# Sheet2.net
KiCad netlist of a schematic drawn in Altium Designer
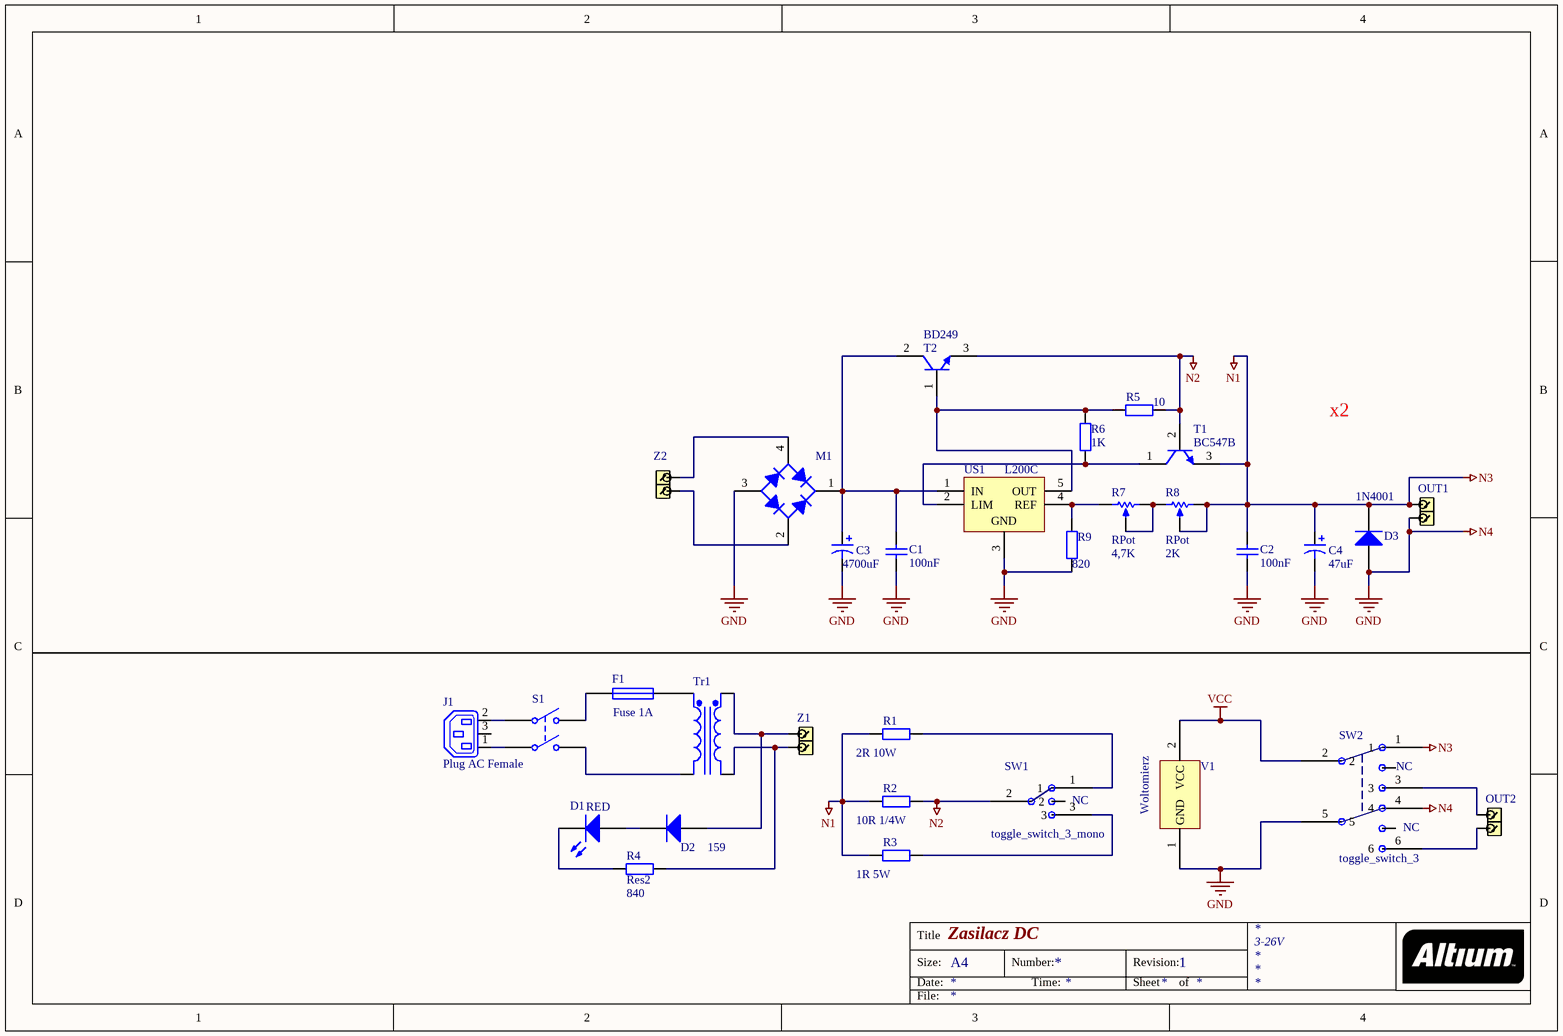
[diagram p0: Sheet2.SchDoc]

(export (version "E")
  (design (tool "Eeschema 10.0.6"))
  (components
    (comp (ref "C1")
      (value "100nF")
      (footprint "CAPR2.54-5.1x2.5")
      (description "Capacitor (Semiconductor SIM Model)")
      (fields (field (name "Comment") "Cap Semi") (field (name "PUBLISHER") "Altium Limited"))
      (libsource (lib "Miscellaneous Devices") (part "Cap Semi"))
    )
    (comp (ref "C2")
      (value "100nF")
      (footprint "CAPR2.54-5.1x2.5")
      (description "Capacitor (Semiconductor SIM Model)")
      (fields (field (name "Comment") "Cap Semi") (field (name "PUBLISHER") "Altium Limited"))
      (libsource (lib "Miscellaneous Devices") (part "Cap Semi"))
    )
    (comp (ref "C3")
      (value "4700uF")
      (footprint "CAPPR7.5-16x20")
      (description "Polarized Capacitor (Radial)")
      (fields (field (name "Comment") "Cap Pol1") (field (name "PUBLISHER") "Altium Limited"))
      (libsource (lib "Miscellaneous Devices") (part "Cap Pol1"))
    )
    (comp (ref "C4")
      (value "47uF")
      (footprint "CAPPR5-6.3x15")
      (description "Polarized Capacitor (Radial)")
      (fields (field (name "Comment") "Cap Pol1") (field (name "PUBLISHER") "Altium Limited"))
      (libsource (lib "Miscellaneous Devices") (part "Cap Pol1"))
    )
    (comp (ref "D1")
      (value "RED")
      (footprint "LED-0")
      (description "Typical INFRARED GaAs LED")
      (fields (field (name "PUBLISHER") "Altium Limited"))
      (libsource (lib "Miscellaneous Devices") (part "LED0"))
    )
    (comp (ref "D2")
      (value "159")
      (footprint "SMC")
      (description "Default Diode")
      (fields (field (name "PUBLISHER") "Altium Limited"))
      (libsource (lib "Miscellaneous Devices") (part "Diode"))
    )
    (comp (ref "D3")
      (value "1N4001")
      (footprint "DO-41")
      (description "1 Amp General Purpose Rectifier")
      (fields (field (name "PUBLISHER") "Altium Limited"))
      (libsource (lib "Miscellaneous Devices") (part "Diode 1N4001"))
    )
    (comp (ref "F1")
      (value "Fuse 1A")
      (footprint "PIN-W2/E2.8")
      (description "Fuse")
      (fields (field (name "PUBLISHER") "Altium Limited"))
      (libsource (lib "Miscellaneous Devices") (part "Fuse 1"))
    )
    (comp (ref "J1")
      (value "Plug AC Female")
      (footprint "IEC7-2H3")
      (description "IEC Mains Power Outlet, EN60 320-2-2 F Class I, PC Flange Rear Mount, Chassis Socket")
      (fields (field (name "PUBLISHER") "Altium Limited"))
      (libsource (lib "Miscellaneous Connectors") (part "Plug AC Female"))
    )
    (comp (ref "M1")
      (value "Bridge1")
      (footprint "D-38")
      (description "Full Wave Diode Bridge")
      (fields (field (name "PUBLISHER") "Altium Limited"))
      (libsource (lib "Miscellaneous Devices") (part "Bridge1"))
    )
    (comp (ref "OUT1") (value "ARK") (footprint "ARK2") (libsource (lib "") (part "ARK_1")))
    (comp (ref "OUT2") (value "ARK") (footprint "ARK2") (libsource (lib "") (part "ARK_1")))
    (comp (ref "R1")
      (value "2R 10W")
      (footprint "AXIAL-0.4")
      (description "Resistor")
      (fields (field (name "Comment") "Res2") (field (name "PUBLISHER") "Altium Limited"))
      (libsource (lib "Miscellaneous Devices") (part "Res2"))
    )
    (comp (ref "R2")
      (value "10R 1/4W")
      (footprint "AXIAL-0.4")
      (description "Resistor")
      (fields (field (name "Comment") "Res2") (field (name "PUBLISHER") "Altium Limited"))
      (libsource (lib "Miscellaneous Devices") (part "Res2"))
    )
    (comp (ref "R3")
      (value "1R 5W")
      (footprint "AXIAL-0.4")
      (description "Resistor")
      (fields (field (name "Comment") "Res2") (field (name "PUBLISHER") "Altium Limited"))
      (libsource (lib "Miscellaneous Devices") (part "Res2"))
    )
    (comp (ref "R4")
      (value "Res2")
      (footprint "AXIAL-0.4")
      (description "Resistor")
      (fields (field (name "ALTIUM_VALUE") "840") (field (name "PUBLISHER") "Altium Limited"))
      (libsource (lib "Miscellaneous Devices") (part "Res2"))
    )
    (comp (ref "R5")
      (value "10")
      (footprint "AXIAL-0.4")
      (description "Resistor")
      (fields (field (name "Comment") "Res2") (field (name "PUBLISHER") "Altium Limited"))
      (libsource (lib "Miscellaneous Devices") (part "Res2"))
    )
    (comp (ref "R6")
      (value "1K")
      (footprint "AXIAL-0.4")
      (description "Resistor")
      (fields (field (name "Comment") "Res2") (field (name "PUBLISHER") "Altium Limited"))
      (libsource (lib "") (part "Res2_1"))
    )
    (comp (ref "R7")
      (value "RPot")
      (footprint "VR5")
      (description "Potentiometer")
      (fields (field (name "ALTIUM_VALUE") "4,7K") (field (name "PUBLISHER") "Altium Limited"))
      (libsource (lib "Miscellaneous Devices") (part "RPot"))
    )
    (comp (ref "R8")
      (value "RPot")
      (footprint "VR5")
      (description "Potentiometer")
      (fields (field (name "ALTIUM_VALUE") "2K") (field (name "PUBLISHER") "Altium Limited"))
      (libsource (lib "Miscellaneous Devices") (part "RPot"))
    )
    (comp (ref "R9")
      (value "820")
      (footprint "AXIAL-0.4")
      (description "Resistor")
      (fields (field (name "Comment") "Res2") (field (name "PUBLISHER") "Altium Limited"))
      (libsource (lib "") (part "Res2_2"))
    )
    (comp (ref "S1")
      (value "SW-DPST")
      (footprint "DPST-4")
      (description "Double-Pole, Single-Throw Switch")
      (fields (field (name "PUBLISHER") "Altium Limited"))
      (libsource (lib "Miscellaneous Devices") (part "SW-DPST"))
    )
    (comp (ref "SW1")
      (value "toggle_switch_3_mono")
      (description "Single 3-stage toggle switch")
      (libsource (lib "zasilacz_lib") (part "toggle_switch_3_mono"))
    )
    (comp (ref "SW2")
      (value "toggle_switch_3")
      (description "Dual 3-stage toggle switch")
      (libsource (lib "zasilacz_lib") (part "toggle_switch_3"))
    )
    (comp (ref "T1")
      (value "BC547B")
      (footprint "ONSC-TO-92-3-29-11")
      (description "Amplifier Transistor, NPN Silicon, 3-Pin TO-92, Bulk Box")
      (fields (field (name "MANUFACTURER") "On Semiconductor"))
      (libsource (lib "ON Semi General Purpose Transistors") (part "BC547B"))
    )
    (comp (ref "T2")
      (value "BD249")
      (footprint "ONSC-TO-220-3-221A-09")
      (description "NPN Silicon Power Transistor, 3-Pin TO-220, Tube")
      (fields (field (name "MANUFACTURER") "On Semiconductor") (field (name "PARTNUMBER") "BUV27"))
      (libsource (lib "ON Semi General Purpose Transistors") (part "BUV27"))
    )
    (comp (ref "Tr1")
      (value "Trans Cupl")
      (footprint "TRF_4")
      (description "Transformer (Coupled Inductor Model)")
      (fields (field (name "PUBLISHER") "Altium Limited"))
      (libsource (lib "Miscellaneous Devices") (part "Trans Cupl"))
    )
    (comp (ref "US1")
      (value "L200C")
      (footprint "PentawattV")
      (description "Adjustable Voltage and Current Regulator, 5-Pin Pentawatt, Tube")
      (fields (field (name "PARTNUMBER") "L200CV"))
      (libsource (lib "ST Microelectronics Power Management Linear Regulator") (part "L200CV"))
    )
    (comp (ref "V1") (value "Woltomierz") (libsource (lib "zasilacz_lib") (part "woltomierz")))
    (comp (ref "Z1") (value "~") (footprint "ARK2") (libsource (lib "") (part "ARK_1")))
    (comp (ref "Z2") (value "~") (footprint "ARK2") (libsource (lib "MOJASIM") (part "ARK")))
  )
  (nets
    (net (code "1") (name "GND") (class "Default")
      (node (ref "C1") (pin "1") (pinfunction "1_1") (pintype "passive"))
      (node (ref "C2") (pin "1") (pinfunction "1_1") (pintype "passive"))
      (node (ref "C3") (pin "2") (pinfunction "2_2") (pintype "passive"))
      (node (ref "C4") (pin "2") (pinfunction "2_2") (pintype "passive"))
      (node (ref "D3") (pin "1") (pinfunction "A_1") (pintype "passive"))
      (node (ref "M1") (pin "3") (pinfunction "A_3") (pintype "passive"))
      (node (ref "OUT1") (pin "1") (pinfunction "1_1") (pintype "passive"))
      (node (ref "R9") (pin "1") (pinfunction "1_1") (pintype "passive"))
      (node (ref "SW2") (pin "4") (pinfunction "4_4") (pintype "passive"))
      (node (ref "SW2") (pin "5") (pinfunction "5_5") (pintype "passive"))
      (node (ref "US1") (pin "3") (pinfunction "GND_3") (pintype "power_in"))
      (node (ref "V1") (pin "1") (pinfunction "GND_1") (pintype "passive"))
    )
    (net (code "2") (name "N1") (class "Default")
      (node (ref "C2") (pin "2") (pinfunction "2_2") (pintype "passive"))
      (node (ref "C4") (pin "1") (pinfunction "1_1") (pintype "passive"))
      (node (ref "D3") (pin "2") (pinfunction "K_2") (pintype "passive"))
      (node (ref "OUT1") (pin "2") (pinfunction "2_2") (pintype "passive"))
      (node (ref "R1") (pin "1") (pinfunction "1_1") (pintype "passive"))
      (node (ref "R2") (pin "1") (pinfunction "1_1") (pintype "passive"))
      (node (ref "R3") (pin "1") (pinfunction "1_1") (pintype "passive"))
      (node (ref "R8") (pin "2") (pinfunction "BOT_2") (pintype "passive"))
      (node (ref "R8") (pin "3") (pinfunction "TAP_3") (pintype "passive"))
      (node (ref "SW2") (pin "1") (pinfunction "1_1") (pintype "passive"))
      (node (ref "T1") (pin "3") (pinfunction "E_3") (pintype "passive"))
    )
    (net (code "3") (name "N2") (class "Default")
      (node (ref "R2") (pin "2") (pinfunction "2_2") (pintype "passive"))
      (node (ref "R5") (pin "2") (pinfunction "2_2") (pintype "passive"))
      (node (ref "SW1") (pin "2") (pinfunction "2_2") (pintype "passive"))
      (node (ref "T1") (pin "2") (pinfunction "B_2") (pintype "passive"))
      (node (ref "T2") (pin "3") (pinfunction "E_3") (pintype "passive"))
    )
    (net (code "4") (name "Net-(D1-A)") (class "Default")
      (node (ref "D1") (pin "1") (pinfunction "A_1") (pintype "passive"))
      (node (ref "D2") (pin "2") (pinfunction "K_2") (pintype "passive"))
    )
    (net (code "5") (name "Net-(D1-K)") (class "Default")
      (node (ref "D1") (pin "2") (pinfunction "K_2") (pintype "passive"))
      (node (ref "R4") (pin "1") (pinfunction "1_1") (pintype "passive"))
    )
    (net (code "6") (name "Net-(D2-A)") (class "Default")
      (node (ref "D2") (pin "1") (pinfunction "A_1") (pintype "passive"))
      (node (ref "Tr1") (pin "3") (pinfunction "Sec+_3") (pintype "passive"))
      (node (ref "Z1") (pin "2") (pinfunction "2_2") (pintype "passive"))
    )
    (net (code "7") (name "Net-(J1-L)") (class "Default")
      (node (ref "J1") (pin "1") (pinfunction "L_1") (pintype "power_in"))
      (node (ref "S1") (pin "3") (pinfunction "COMMON2_3") (pintype "passive"))
    )
    (net (code "8") (name "Net-(J1-N)") (class "Default")
      (node (ref "J1") (pin "2") (pinfunction "N_2") (pintype "power_in"))
      (node (ref "S1") (pin "1") (pinfunction "COMMON1_1") (pintype "passive"))
    )
    (net (code "9") (name "Net-(M1-C-Pad2)") (class "Default")
      (node (ref "M1") (pin "2") (pinfunction "C_2") (pintype "passive"))
      (node (ref "Z2") (pin "2") (pinfunction "2_2") (pintype "passive"))
    )
    (net (code "10") (name "Net-(M1-C-Pad4)") (class "Default")
      (node (ref "M1") (pin "4") (pinfunction "C_4") (pintype "passive"))
      (node (ref "Z2") (pin "1") (pinfunction "1_1") (pintype "passive"))
    )
    (net (code "11") (name "Net-(M1-K)") (class "Default")
      (node (ref "C1") (pin "2") (pinfunction "2_2") (pintype "passive"))
      (node (ref "C3") (pin "1") (pinfunction "1_1") (pintype "passive"))
      (node (ref "M1") (pin "1") (pinfunction "K_1") (pintype "passive"))
      (node (ref "T2") (pin "2") (pinfunction "C_2") (pintype "passive"))
      (node (ref "US1") (pin "1") (pinfunction "IN_1") (pintype "power_in"))
    )
    (net (code "12") (name "Net-(OUT2-Pad1)") (class "Default")
      (node (ref "OUT2") (pin "1") (pinfunction "1_1") (pintype "passive"))
      (node (ref "SW2") (pin "6") (pinfunction "6_6") (pintype "passive"))
    )
    (net (code "13") (name "Net-(OUT2-Pad2)") (class "Default")
      (node (ref "OUT2") (pin "2") (pinfunction "2_2") (pintype "passive"))
      (node (ref "SW2") (pin "3") (pinfunction "3_3") (pintype "passive"))
    )
    (net (code "14") (name "Net-(R1-Pad2)") (class "Default")
      (node (ref "R1") (pin "2") (pinfunction "2_2") (pintype "passive"))
      (node (ref "SW1") (pin "1") (pinfunction "1_1") (pintype "passive"))
    )
    (net (code "15") (name "Net-(R3-Pad2)") (class "Default")
      (node (ref "R3") (pin "2") (pinfunction "2_2") (pintype "passive"))
      (node (ref "SW1") (pin "3") (pinfunction "3_3") (pintype "passive"))
    )
    (net (code "16") (name "Net-(R7-BOT)") (class "Default")
      (node (ref "R7") (pin "2") (pinfunction "BOT_2") (pintype "passive"))
      (node (ref "R7") (pin "3") (pinfunction "TAP_3") (pintype "passive"))
      (node (ref "R8") (pin "1") (pinfunction "TOP_1") (pintype "passive"))
    )
    (net (code "17") (name "Net-(R7-TOP)") (class "Default")
      (node (ref "R7") (pin "1") (pinfunction "TOP_1") (pintype "passive"))
      (node (ref "R9") (pin "2") (pinfunction "2_2") (pintype "passive"))
      (node (ref "US1") (pin "4") (pinfunction "REF_4") (pintype "passive"))
    )
    (net (code "18") (name "Net-(S1-NO1)") (class "Default")
      (node (ref "F1") (pin "1") (pinfunction "1_1") (pintype "passive"))
      (node (ref "S1") (pin "2") (pinfunction "NO1_2") (pintype "passive"))
    )
    (net (code "19") (name "Net-(S1-NO2)") (class "Default")
      (node (ref "S1") (pin "4") (pinfunction "NO2_4") (pintype "passive"))
      (node (ref "Tr1") (pin "2") (pinfunction "Pri-_2") (pintype "passive"))
    )
    (net (code "20") (name "Net-(T1-C)") (class "Default")
      (node (ref "R6") (pin "2") (pinfunction "2_2") (pintype "passive"))
      (node (ref "T1") (pin "1") (pinfunction "C_1") (pintype "passive"))
      (node (ref "US1") (pin "2") (pinfunction "LIM_2") (pintype "passive"))
    )
    (net (code "21") (name "Net-(T2-B)") (class "Default")
      (node (ref "R5") (pin "1") (pinfunction "1_1") (pintype "passive"))
      (node (ref "R6") (pin "1") (pinfunction "1_1") (pintype "passive"))
      (node (ref "T2") (pin "1") (pinfunction "B_1") (pintype "passive"))
      (node (ref "US1") (pin "5") (pinfunction "OUT_5") (pintype "power_in"))
    )
    (net (code "22") (name "Net-(Tr1-Pri+)") (class "Default")
      (node (ref "F1") (pin "2") (pinfunction "2_2") (pintype "passive"))
      (node (ref "Tr1") (pin "1") (pinfunction "Pri+_1") (pintype "passive"))
    )
    (net (code "23") (name "Net-(Tr1-Sec-)") (class "Default")
      (node (ref "R4") (pin "2") (pinfunction "2_2") (pintype "passive"))
      (node (ref "Tr1") (pin "4") (pinfunction "Sec-_4") (pintype "passive"))
      (node (ref "Z1") (pin "1") (pinfunction "1_1") (pintype "passive"))
    )
    (net (code "24") (name "VCC") (class "Default")
      (node (ref "SW2") (pin "2") (pinfunction "2_2") (pintype "passive"))
      (node (ref "V1") (pin "2") (pinfunction "VCC_2") (pintype "passive"))
    )
    (net (code "25") (name "unconnected-(J1-E-Pad3)") (class "Default")
      (node (ref "J1") (pin "3") (pinfunction "E_3") (pintype "power_in"))
    )
  )
)
